# aparture_v2.net
KiCad netlist of a schematic drawn in EAGLE
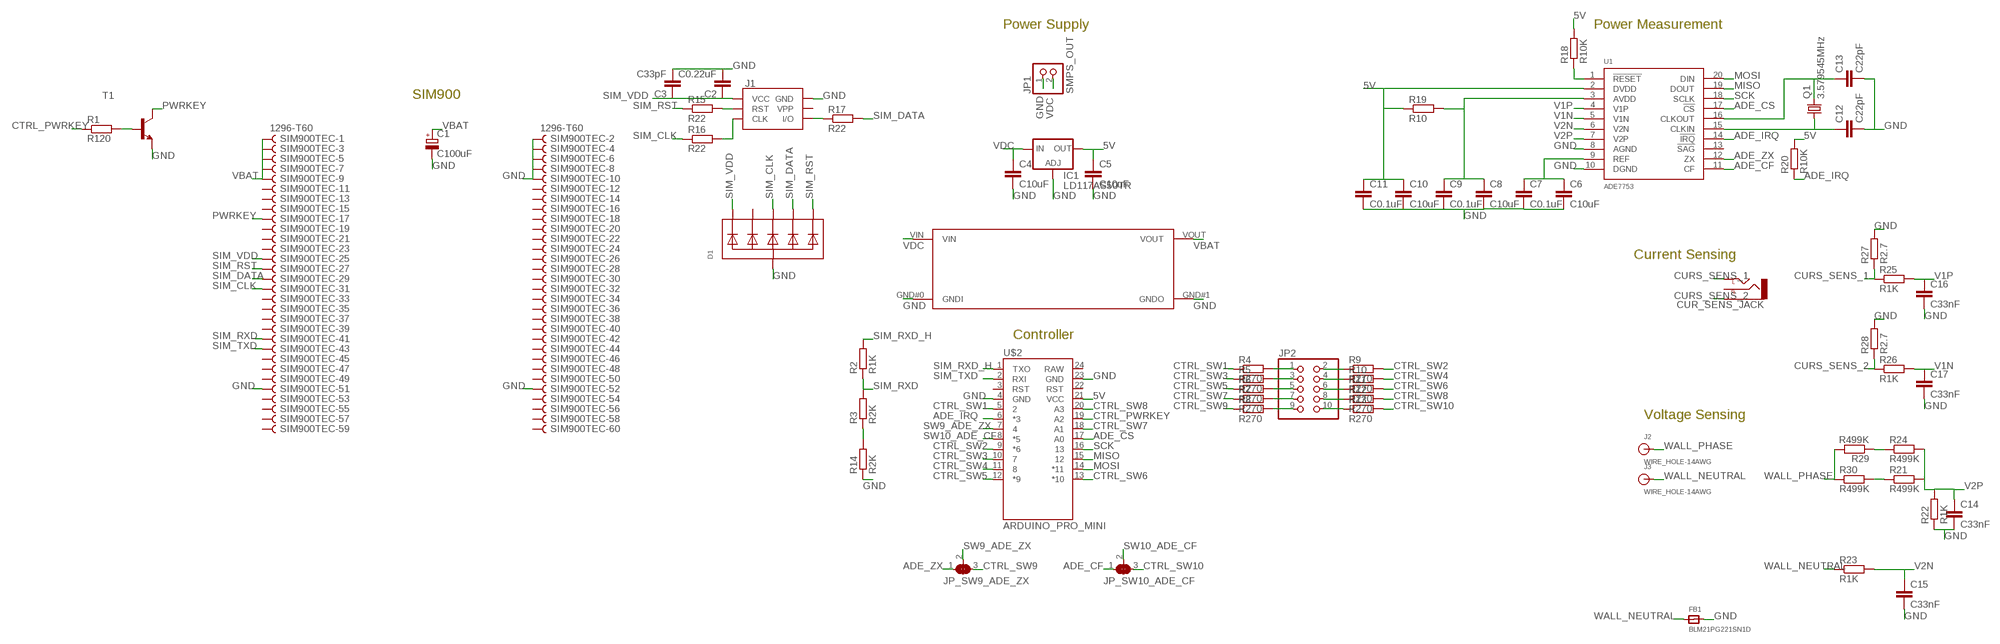
[diagram p0: schematic, sheet 1]

(export (version "E")
  (design (tool "Eeschema 10.0.6"))
  (components
    (comp (ref "C1")
      (value "C100uF")
      (footprint "eagle-import:153CLV-0605")
      (libsource (lib "eagle-import") (part "CPOL-EU153CLV-0605"))
    )
    (comp (ref "C2")
      (value "C0.22uF")
      (footprint "eagle-import:C0805")
      (libsource (lib "eagle-import") (part "C-EUC0805"))
    )
    (comp (ref "C3")
      (value "C33pF")
      (footprint "eagle-import:C0805")
      (libsource (lib "eagle-import") (part "C-EUC0805"))
    )
    (comp (ref "C4")
      (value "C10uF")
      (footprint "eagle-import:C0805")
      (libsource (lib "eagle-import") (part "C-EUC0805"))
    )
    (comp (ref "C5")
      (value "C10uF")
      (footprint "eagle-import:C0805")
      (libsource (lib "eagle-import") (part "C-EUC0805"))
    )
    (comp (ref "C6")
      (value "C10uF")
      (footprint "eagle-import:C0805")
      (libsource (lib "eagle-import") (part "C-EUC0805"))
    )
    (comp (ref "C7")
      (value "C0.1uF")
      (footprint "eagle-import:C0805")
      (libsource (lib "eagle-import") (part "C-EUC0805"))
    )
    (comp (ref "C8")
      (value "C10uF")
      (footprint "eagle-import:C0805")
      (libsource (lib "eagle-import") (part "C-EUC0805"))
    )
    (comp (ref "C9")
      (value "C0.1uF")
      (footprint "eagle-import:C0805")
      (libsource (lib "eagle-import") (part "C-EUC0805"))
    )
    (comp (ref "C10")
      (value "C10uF")
      (footprint "eagle-import:C0805")
      (libsource (lib "eagle-import") (part "C-EUC0805"))
    )
    (comp (ref "C11")
      (value "C0.1uF")
      (footprint "eagle-import:C0805")
      (libsource (lib "eagle-import") (part "C-EUC0805"))
    )
    (comp (ref "C12")
      (value "C22pF")
      (footprint "eagle-import:C0805")
      (libsource (lib "eagle-import") (part "C-EUC0805"))
    )
    (comp (ref "C13")
      (value "C22pF")
      (footprint "eagle-import:C0805")
      (libsource (lib "eagle-import") (part "C-EUC0805"))
    )
    (comp (ref "C14")
      (value "C33nF")
      (footprint "eagle-import:C0805")
      (libsource (lib "eagle-import") (part "C-EUC0805"))
    )
    (comp (ref "C15")
      (value "C33nF")
      (footprint "eagle-import:C0805")
      (libsource (lib "eagle-import") (part "C-EUC0805"))
    )
    (comp (ref "C16")
      (value "C33nF")
      (footprint "eagle-import:C0805")
      (libsource (lib "eagle-import") (part "C-EUC0805"))
    )
    (comp (ref "C17")
      (value "C33nF")
      (footprint "eagle-import:C0805")
      (libsource (lib "eagle-import") (part "C-EUC0805"))
    )
    (comp (ref "CUR_SENS_JACK")
      (value "AUDIO-JACKSMD2")
      (footprint "eagle-import:AUDIO-JACK-3.5MM-SMD")
      (libsource (lib "eagle-import") (part "AUDIO-JACKSMD2"))
    )
    (comp (ref "D1")
      (value "TVSARRAY_5LANE")
      (footprint "eagle-import:SOT363")
      (libsource (lib "eagle-import") (part "TVSARRAY_5LANE"))
    )
    (comp (ref "FB1")
      (value "BLM21PG221SN1D")
      (footprint "eagle-import:0805")
      (libsource (lib "eagle-import") (part "FERRITE0805"))
    )
    (comp (ref "IC1")
      (value "LD117AS50TR")
      (footprint "eagle-import:SOT223")
      (libsource (lib "eagle-import") (part "LD117A?S50TR"))
    )
    (comp (ref "J1")
      (value "SIMHOLDERSIM")
      (footprint "eagle-import:SIMHOLDER")
      (libsource (lib "eagle-import") (part "SIMHOLDERSIM"))
    )
    (comp (ref "J2")
      (value "WIRE_HOLE-14AWG")
      (footprint "eagle-import:WIRE_HOLE-14AWG")
      (libsource (lib "eagle-import") (part "WIRE_HOLE-14AWG"))
    )
    (comp (ref "J3")
      (value "WIRE_HOLE-14AWG")
      (footprint "eagle-import:WIRE_HOLE-14AWG")
      (libsource (lib "eagle-import") (part "WIRE_HOLE-14AWG"))
    )
    (comp (ref "JP1")
      (value "SMPS_OUT")
      (footprint "eagle-import:1X02")
      (libsource (lib "eagle-import") (part "PINHD-1X2"))
    )
    (comp (ref "JP2")
      (value "PINHD-2X5")
      (footprint "eagle-import:2X05")
      (libsource (lib "eagle-import") (part "PINHD-2X5"))
    )
    (comp (ref "JP_SW9_ADE_ZX")
      (value "SOLDERJUMPER_2WAY0603")
      (footprint "eagle-import:SOLDERJUMPER_2WAY_OPEN_0603")
      (libsource (lib "eagle-import") (part "SOLDERJUMPER_2WAY0603"))
    )
    (comp (ref "JP_SW10_ADE_CF")
      (value "SOLDERJUMPER_2WAY0603")
      (footprint "eagle-import:SOLDERJUMPER_2WAY_OPEN_0603")
      (libsource (lib "eagle-import") (part "SOLDERJUMPER_2WAY0603"))
    )
    (comp (ref "Q1")
      (value "3.579545MHz")
      (footprint "eagle-import:HC49_S")
      (libsource (lib "eagle-import") (part "CRYSTALHC49S"))
    )
    (comp (ref "R1")
      (value "R120")
      (footprint "eagle-import:R0805")
      (libsource (lib "eagle-import") (part "R-EU_R0805"))
    )
    (comp (ref "R2")
      (value "R1K")
      (footprint "eagle-import:M0805")
      (libsource (lib "eagle-import") (part "R-EU_M0805"))
    )
    (comp (ref "R3")
      (value "R2K")
      (footprint "eagle-import:M0805")
      (libsource (lib "eagle-import") (part "R-EU_M0805"))
    )
    (comp (ref "R4")
      (value "R270")
      (footprint "eagle-import:R0603")
      (libsource (lib "eagle-import") (part "R-EU_R0603"))
    )
    (comp (ref "R5")
      (value "R270")
      (footprint "eagle-import:R0603")
      (libsource (lib "eagle-import") (part "R-EU_R0603"))
    )
    (comp (ref "R6")
      (value "R270")
      (footprint "eagle-import:R0603")
      (libsource (lib "eagle-import") (part "R-EU_R0603"))
    )
    (comp (ref "R7")
      (value "R270")
      (footprint "eagle-import:R0603")
      (libsource (lib "eagle-import") (part "R-EU_R0603"))
    )
    (comp (ref "R8")
      (value "R270")
      (footprint "eagle-import:R0603")
      (libsource (lib "eagle-import") (part "R-EU_R0603"))
    )
    (comp (ref "R9")
      (value "R270")
      (footprint "eagle-import:R0603")
      (libsource (lib "eagle-import") (part "R-EU_R0603"))
    )
    (comp (ref "R10")
      (value "R270")
      (footprint "eagle-import:R0603")
      (libsource (lib "eagle-import") (part "R-EU_R0603"))
    )
    (comp (ref "R11")
      (value "R270")
      (footprint "eagle-import:R0603")
      (libsource (lib "eagle-import") (part "R-EU_R0603"))
    )
    (comp (ref "R12")
      (value "R270")
      (footprint "eagle-import:R0603")
      (libsource (lib "eagle-import") (part "R-EU_R0603"))
    )
    (comp (ref "R13")
      (value "R270")
      (footprint "eagle-import:R0603")
      (libsource (lib "eagle-import") (part "R-EU_R0603"))
    )
    (comp (ref "R14")
      (value "R2K")
      (footprint "eagle-import:M0805")
      (libsource (lib "eagle-import") (part "R-EU_M0805"))
    )
    (comp (ref "R15")
      (value "R22")
      (footprint "eagle-import:R0603")
      (libsource (lib "eagle-import") (part "R-EU_R0603"))
    )
    (comp (ref "R16")
      (value "R22")
      (footprint "eagle-import:R0603")
      (libsource (lib "eagle-import") (part "R-EU_R0603"))
    )
    (comp (ref "R17")
      (value "R22")
      (footprint "eagle-import:R0603")
      (libsource (lib "eagle-import") (part "R-EU_R0603"))
    )
    (comp (ref "R18")
      (value "R10K")
      (footprint "eagle-import:R0805")
      (libsource (lib "eagle-import") (part "R-EU_R0805"))
    )
    (comp (ref "R19")
      (value "R10")
      (footprint "eagle-import:R0805")
      (libsource (lib "eagle-import") (part "R-EU_R0805"))
    )
    (comp (ref "R20")
      (value "R10K")
      (footprint "eagle-import:R0805")
      (libsource (lib "eagle-import") (part "R-EU_R0805"))
    )
    (comp (ref "R21")
      (value "R499K")
      (footprint "eagle-import:R0805")
      (libsource (lib "eagle-import") (part "R-EU_R0805"))
    )
    (comp (ref "R22")
      (value "R1K")
      (footprint "eagle-import:R0805")
      (libsource (lib "eagle-import") (part "R-EU_R0805"))
    )
    (comp (ref "R23")
      (value "R1K")
      (footprint "eagle-import:R0805")
      (libsource (lib "eagle-import") (part "R-EU_R0805"))
    )
    (comp (ref "R24")
      (value "R499K")
      (footprint "eagle-import:0309V")
      (libsource (lib "eagle-import") (part "R-EU_0309/V"))
    )
    (comp (ref "R25")
      (value "R1K")
      (footprint "eagle-import:R0805")
      (libsource (lib "eagle-import") (part "R-EU_R0805"))
    )
    (comp (ref "R26")
      (value "R1K")
      (footprint "eagle-import:R0805")
      (libsource (lib "eagle-import") (part "R-EU_R0805"))
    )
    (comp (ref "R27")
      (value "R2.7")
      (footprint "eagle-import:0309V")
      (libsource (lib "eagle-import") (part "R-EU_0309/V"))
    )
    (comp (ref "R28")
      (value "R2.7")
      (footprint "eagle-import:0309V")
      (libsource (lib "eagle-import") (part "R-EU_0309/V"))
    )
    (comp (ref "R29")
      (value "R499K")
      (footprint "eagle-import:0309V")
      (libsource (lib "eagle-import") (part "R-EU_0309/V"))
    )
    (comp (ref "R30")
      (value "R499K")
      (footprint "eagle-import:R0805")
      (libsource (lib "eagle-import") (part "R-EU_R0805"))
    )
    (comp (ref "SIM900TEC")
      (value "1296-T60")
      (footprint "eagle-import:1296-60")
      (libsource (lib "eagle-import") (part "1296-T60"))
    )
    (comp (ref "T1")
      (value "MMBT2222ALT1-NPN-SOT23-BEC")
      (footprint "eagle-import:SOT23-BEC")
      (libsource (lib "eagle-import") (part "-NPN-SOT23-BECMMBT2222ALT1"))
    )
    (comp (ref "U$1")
      (value "DCDCMODULE")
      (footprint "eagle-import:DCDCMODULE")
      (libsource (lib "eagle-import") (part "DCDCMODULE"))
    )
    (comp (ref "U$2")
      (value "ARDUINO_PRO_MINI")
      (footprint "eagle-import:ARDUINO_PRO_MINI")
      (libsource (lib "eagle-import") (part "ARDUINO_PRO_MINI"))
    )
    (comp (ref "U1")
      (value "ADE7753")
      (footprint "eagle-import:SSOP-20")
      (libsource (lib "eagle-import") (part "ADE7753"))
    )
  )
  (nets
    (net (code "1") (name "/5V") (class "Default")
      (node (ref "C10") (pin "1") (pinfunction "1_1") (pintype "passive"))
      (node (ref "C11") (pin "1") (pinfunction "1_1") (pintype "passive"))
      (node (ref "C5") (pin "1") (pinfunction "1_1") (pintype "passive"))
      (node (ref "IC1") (pin "4") (pinfunction "OUT_4") (pintype "passive"))
      (node (ref "R18") (pin "2") (pinfunction "2_2") (pintype "passive"))
      (node (ref "R19") (pin "1") (pinfunction "1_1") (pintype "passive"))
      (node (ref "R20") (pin "2") (pinfunction "2_2") (pintype "passive"))
      (node (ref "U$2") (pin "21") (pinfunction "VCC_21") (pintype "bidirectional"))
      (node (ref "U1") (pin "2") (pinfunction "DVDD_2") (pintype "bidirectional"))
    )
    (net (code "2") (name "/ADE_CF") (class "Default")
      (node (ref "JP_SW10_ADE_CF") (pin "1") (pinfunction "1_1") (pintype "passive"))
      (node (ref "U1") (pin "11") (pinfunction "CF_11") (pintype "bidirectional"))
    )
    (net (code "3") (name "/ADE_CS") (class "Default")
      (node (ref "U$2") (pin "17") (pinfunction "A0_17") (pintype "bidirectional"))
      (node (ref "U1") (pin "17") (pinfunction "~{CS}_17") (pintype "bidirectional"))
    )
    (net (code "4") (name "/ADE_IRQ") (class "Default")
      (node (ref "R20") (pin "1") (pinfunction "1_1") (pintype "passive"))
      (node (ref "U$2") (pin "6") (pinfunction "*3_6") (pintype "bidirectional"))
      (node (ref "U1") (pin "14") (pinfunction "~{IRQ}_14") (pintype "bidirectional"))
    )
    (net (code "5") (name "/ADE_ZX") (class "Default")
      (node (ref "JP_SW9_ADE_ZX") (pin "1") (pinfunction "1_1") (pintype "passive"))
      (node (ref "U1") (pin "12") (pinfunction "ZX_12") (pintype "bidirectional"))
    )
    (net (code "6") (name "/CTRL_PWRKEY") (class "Default")
      (node (ref "R1") (pin "1") (pinfunction "1_1") (pintype "passive"))
      (node (ref "U$2") (pin "19") (pinfunction "A2_19") (pintype "bidirectional"))
    )
    (net (code "7") (name "/CTRL_SW1") (class "Default")
      (node (ref "R4") (pin "1") (pinfunction "1_1") (pintype "passive"))
      (node (ref "U$2") (pin "5") (pinfunction "2_5") (pintype "bidirectional"))
    )
    (net (code "8") (name "/CTRL_SW2") (class "Default")
      (node (ref "R9") (pin "2") (pinfunction "2_2") (pintype "passive"))
      (node (ref "U$2") (pin "9") (pinfunction "*6_9") (pintype "bidirectional"))
    )
    (net (code "9") (name "/CTRL_SW3") (class "Default")
      (node (ref "R5") (pin "1") (pinfunction "1_1") (pintype "passive"))
      (node (ref "U$2") (pin "10") (pinfunction "7_10") (pintype "bidirectional"))
    )
    (net (code "10") (name "/CTRL_SW4") (class "Default")
      (node (ref "R10") (pin "2") (pinfunction "2_2") (pintype "passive"))
      (node (ref "U$2") (pin "11") (pinfunction "8_11") (pintype "bidirectional"))
    )
    (net (code "11") (name "/CTRL_SW5") (class "Default")
      (node (ref "R6") (pin "1") (pinfunction "1_1") (pintype "passive"))
      (node (ref "U$2") (pin "12") (pinfunction "*9_12") (pintype "bidirectional"))
    )
    (net (code "12") (name "/CTRL_SW6") (class "Default")
      (node (ref "R11") (pin "2") (pinfunction "2_2") (pintype "passive"))
      (node (ref "U$2") (pin "13") (pinfunction "*10_13") (pintype "bidirectional"))
    )
    (net (code "13") (name "/CTRL_SW7") (class "Default")
      (node (ref "R7") (pin "1") (pinfunction "1_1") (pintype "passive"))
      (node (ref "U$2") (pin "18") (pinfunction "A1_18") (pintype "bidirectional"))
    )
    (net (code "14") (name "/CTRL_SW8") (class "Default")
      (node (ref "R12") (pin "2") (pinfunction "2_2") (pintype "passive"))
      (node (ref "U$2") (pin "20") (pinfunction "A3_20") (pintype "bidirectional"))
    )
    (net (code "15") (name "/CTRL_SW9") (class "Default")
      (node (ref "JP_SW9_ADE_ZX") (pin "3") (pinfunction "3_3") (pintype "passive"))
      (node (ref "R8") (pin "1") (pinfunction "1_1") (pintype "passive"))
    )
    (net (code "16") (name "/CTRL_SW10") (class "Default")
      (node (ref "JP_SW10_ADE_CF") (pin "3") (pinfunction "3_3") (pintype "passive"))
      (node (ref "R13") (pin "2") (pinfunction "2_2") (pintype "passive"))
    )
    (net (code "17") (name "/CURS_SENS_1") (class "Default")
      (node (ref "CUR_SENS_JACK") (pin "TIP") (pinfunction "LEFT_TIP") (pintype "bidirectional"))
      (node (ref "R25") (pin "1") (pinfunction "1_1") (pintype "passive"))
      (node (ref "R27") (pin "1") (pinfunction "1_1") (pintype "passive"))
    )
    (net (code "18") (name "/CURS_SENS_2") (class "Default")
      (node (ref "CUR_SENS_JACK") (pin "SLEEVE") (pinfunction "SLEEVE_SLEEVE") (pintype "bidirectional"))
      (node (ref "R26") (pin "1") (pinfunction "1_1") (pintype "passive"))
      (node (ref "R28") (pin "1") (pinfunction "1_1") (pintype "passive"))
    )
    (net (code "19") (name "/GND") (class "Default")
      (node (ref "C1") (pin "-") (pinfunction "-_-") (pintype "passive"))
      (node (ref "C10") (pin "2") (pinfunction "2_2") (pintype "passive"))
      (node (ref "C11") (pin "2") (pinfunction "2_2") (pintype "passive"))
      (node (ref "C12") (pin "2") (pinfunction "2_2") (pintype "passive"))
      (node (ref "C13") (pin "2") (pinfunction "2_2") (pintype "passive"))
      (node (ref "C14") (pin "2") (pinfunction "2_2") (pintype "passive"))
      (node (ref "C15") (pin "2") (pinfunction "2_2") (pintype "passive"))
      (node (ref "C16") (pin "2") (pinfunction "2_2") (pintype "passive"))
      (node (ref "C17") (pin "2") (pinfunction "2_2") (pintype "passive"))
      (node (ref "C2") (pin "2") (pinfunction "2_2") (pintype "passive"))
      (node (ref "C3") (pin "2") (pinfunction "2_2") (pintype "passive"))
      (node (ref "C4") (pin "2") (pinfunction "2_2") (pintype "passive"))
      (node (ref "C5") (pin "2") (pinfunction "2_2") (pintype "passive"))
      (node (ref "C6") (pin "2") (pinfunction "2_2") (pintype "passive"))
      (node (ref "C7") (pin "2") (pinfunction "2_2") (pintype "passive"))
      (node (ref "C8") (pin "2") (pinfunction "2_2") (pintype "passive"))
      (node (ref "C9") (pin "2") (pinfunction "2_2") (pintype "passive"))
      (node (ref "D1") (pin "2") (pinfunction "A_2") (pintype "passive"))
      (node (ref "FB1") (pin "2") (pinfunction "P$2_2") (pintype "passive"))
      (node (ref "IC1") (pin "1") (pinfunction "ADJ_1") (pintype "input"))
      (node (ref "J1") (pin "C5") (pinfunction "GND_C5") (pintype "power_in"))
      (node (ref "JP1") (pin "1") (pinfunction "1_1") (pintype "passive"))
      (node (ref "R14") (pin "1") (pinfunction "1_1") (pintype "passive"))
      (node (ref "R22") (pin "1") (pinfunction "1_1") (pintype "passive"))
      (node (ref "R27") (pin "2") (pinfunction "2_2") (pintype "passive"))
      (node (ref "R28") (pin "2") (pinfunction "2_2") (pintype "passive"))
      (node (ref "SIM900TEC") (pin "10") (pinfunction "B_10") (pintype "passive"))
      (node (ref "SIM900TEC") (pin "2") (pinfunction "B_2") (pintype "passive"))
      (node (ref "SIM900TEC") (pin "4") (pinfunction "B_4") (pintype "passive"))
      (node (ref "SIM900TEC") (pin "51") (pinfunction "B_51") (pintype "passive"))
      (node (ref "SIM900TEC") (pin "52") (pinfunction "B_52") (pintype "passive"))
      (node (ref "SIM900TEC") (pin "6") (pinfunction "B_6") (pintype "passive"))
      (node (ref "SIM900TEC") (pin "8") (pinfunction "B_8") (pintype "passive"))
      (node (ref "T1") (pin "E") (pinfunction "E_E") (pintype "passive"))
      (node (ref "U$1") (pin "GND#0") (pinfunction "GNDI_GND#0") (pintype "bidirectional"))
      (node (ref "U$1") (pin "GND#1") (pinfunction "GNDO_GND#1") (pintype "bidirectional"))
      (node (ref "U$2") (pin "23") (pinfunction "GND_23") (pintype "bidirectional"))
      (node (ref "U$2") (pin "4") (pinfunction "GND_4") (pintype "bidirectional"))
      (node (ref "U1") (pin "10") (pinfunction "DGND_10") (pintype "bidirectional"))
      (node (ref "U1") (pin "8") (pinfunction "AGND_8") (pintype "bidirectional"))
    )
    (net (code "20") (name "/MISO") (class "Default")
      (node (ref "U$2") (pin "15") (pinfunction "12_15") (pintype "bidirectional"))
      (node (ref "U1") (pin "19") (pinfunction "DOUT_19") (pintype "bidirectional"))
    )
    (net (code "21") (name "/MOSI") (class "Default")
      (node (ref "U$2") (pin "14") (pinfunction "*11_14") (pintype "bidirectional"))
      (node (ref "U1") (pin "20") (pinfunction "DIN_20") (pintype "bidirectional"))
    )
    (net (code "22") (name "/PWRKEY") (class "Default")
      (node (ref "SIM900TEC") (pin "17") (pinfunction "B_17") (pintype "passive"))
      (node (ref "T1") (pin "C") (pinfunction "C_C") (pintype "passive"))
    )
    (net (code "23") (name "/SCK") (class "Default")
      (node (ref "U$2") (pin "16") (pinfunction "13_16") (pintype "bidirectional"))
      (node (ref "U1") (pin "18") (pinfunction "SCLK_18") (pintype "bidirectional"))
    )
    (net (code "24") (name "/SIM_CLK") (class "Default")
      (node (ref "D1") (pin "4") (pinfunction "C3_4") (pintype "passive"))
      (node (ref "R16") (pin "1") (pinfunction "1_1") (pintype "passive"))
      (node (ref "SIM900TEC") (pin "31") (pinfunction "B_31") (pintype "passive"))
    )
    (net (code "25") (name "/SIM_DATA") (class "Default")
      (node (ref "D1") (pin "5") (pinfunction "C4_5") (pintype "passive"))
      (node (ref "R17") (pin "2") (pinfunction "2_2") (pintype "passive"))
      (node (ref "SIM900TEC") (pin "29") (pinfunction "B_29") (pintype "passive"))
    )
    (net (code "26") (name "/SIM_RST") (class "Default")
      (node (ref "D1") (pin "6") (pinfunction "C5_6") (pintype "passive"))
      (node (ref "R15") (pin "1") (pinfunction "1_1") (pintype "passive"))
      (node (ref "SIM900TEC") (pin "27") (pinfunction "B_27") (pintype "passive"))
    )
    (net (code "27") (name "/SIM_RXD") (class "Default")
      (node (ref "R2") (pin "1") (pinfunction "1_1") (pintype "passive"))
      (node (ref "R3") (pin "2") (pinfunction "2_2") (pintype "passive"))
      (node (ref "SIM900TEC") (pin "41") (pinfunction "B_41") (pintype "passive"))
    )
    (net (code "28") (name "/SIM_RXD_H") (class "Default")
      (node (ref "R2") (pin "2") (pinfunction "2_2") (pintype "passive"))
      (node (ref "U$2") (pin "1") (pinfunction "TXO_1") (pintype "bidirectional"))
    )
    (net (code "29") (name "/SIM_TXD") (class "Default")
      (node (ref "SIM900TEC") (pin "43") (pinfunction "B_43") (pintype "passive"))
      (node (ref "U$2") (pin "2") (pinfunction "RXI_2") (pintype "bidirectional"))
    )
    (net (code "30") (name "/SIM_VDD") (class "Default")
      (node (ref "C2") (pin "1") (pinfunction "1_1") (pintype "passive"))
      (node (ref "C3") (pin "1") (pinfunction "1_1") (pintype "passive"))
      (node (ref "D1") (pin "1") (pinfunction "C1_1") (pintype "passive"))
      (node (ref "J1") (pin "C1") (pinfunction "VCC_C1") (pintype "power_in"))
      (node (ref "SIM900TEC") (pin "25") (pinfunction "B_25") (pintype "passive"))
    )
    (net (code "31") (name "/SW9_ADE_ZX") (class "Default")
      (node (ref "JP_SW9_ADE_ZX") (pin "2") (pinfunction "2_2") (pintype "passive"))
      (node (ref "U$2") (pin "7") (pinfunction "4_7") (pintype "bidirectional"))
    )
    (net (code "32") (name "/SW10_ADE_CF") (class "Default")
      (node (ref "JP_SW10_ADE_CF") (pin "2") (pinfunction "2_2") (pintype "passive"))
      (node (ref "U$2") (pin "8") (pinfunction "*5_8") (pintype "bidirectional"))
    )
    (net (code "33") (name "/V1N") (class "Default")
      (node (ref "C17") (pin "1") (pinfunction "1_1") (pintype "passive"))
      (node (ref "R26") (pin "2") (pinfunction "2_2") (pintype "passive"))
      (node (ref "U1") (pin "5") (pinfunction "V1N_5") (pintype "bidirectional"))
    )
    (net (code "34") (name "/V1P") (class "Default")
      (node (ref "C16") (pin "1") (pinfunction "1_1") (pintype "passive"))
      (node (ref "R25") (pin "2") (pinfunction "2_2") (pintype "passive"))
      (node (ref "U1") (pin "4") (pinfunction "V1P_4") (pintype "bidirectional"))
    )
    (net (code "35") (name "/V2N") (class "Default")
      (node (ref "C15") (pin "1") (pinfunction "1_1") (pintype "passive"))
      (node (ref "R23") (pin "2") (pinfunction "2_2") (pintype "passive"))
      (node (ref "U1") (pin "6") (pinfunction "V2N_6") (pintype "bidirectional"))
    )
    (net (code "36") (name "/V2P") (class "Default")
      (node (ref "C14") (pin "1") (pinfunction "1_1") (pintype "passive"))
      (node (ref "R21") (pin "2") (pinfunction "2_2") (pintype "passive"))
      (node (ref "R22") (pin "2") (pinfunction "2_2") (pintype "passive"))
      (node (ref "R24") (pin "2") (pinfunction "2_2") (pintype "passive"))
      (node (ref "U1") (pin "7") (pinfunction "V2P_7") (pintype "bidirectional"))
    )
    (net (code "37") (name "/VBAT") (class "Default")
      (node (ref "C1") (pin "+") (pinfunction "+_+") (pintype "passive"))
      (node (ref "SIM900TEC") (pin "1") (pinfunction "B_1") (pintype "passive"))
      (node (ref "SIM900TEC") (pin "3") (pinfunction "B_3") (pintype "passive"))
      (node (ref "SIM900TEC") (pin "5") (pinfunction "B_5") (pintype "passive"))
      (node (ref "SIM900TEC") (pin "7") (pinfunction "B_7") (pintype "passive"))
      (node (ref "SIM900TEC") (pin "9") (pinfunction "B_9") (pintype "passive"))
      (node (ref "U$1") (pin "VOUT") (pinfunction "VOUT_VOUT") (pintype "bidirectional"))
    )
    (net (code "38") (name "/VDC") (class "Default")
      (node (ref "C4") (pin "1") (pinfunction "1_1") (pintype "passive"))
      (node (ref "IC1") (pin "3") (pinfunction "IN_3") (pintype "input"))
      (node (ref "JP1") (pin "2") (pinfunction "2_2") (pintype "passive"))
      (node (ref "U$1") (pin "VIN") (pinfunction "VIN_VIN") (pintype "bidirectional"))
    )
    (net (code "39") (name "/WALL_NEUTRAL") (class "Default")
      (node (ref "FB1") (pin "1") (pinfunction "P$1_1") (pintype "passive"))
      (node (ref "J3") (pin "P$1") (pinfunction "P$1_P$1") (pintype "bidirectional"))
      (node (ref "R23") (pin "1") (pinfunction "1_1") (pintype "passive"))
    )
    (net (code "40") (name "/WALL_PHASE") (class "Default")
      (node (ref "J2") (pin "P$1") (pinfunction "P$1_P$1") (pintype "bidirectional"))
      (node (ref "R29") (pin "2") (pinfunction "2_2") (pintype "passive"))
      (node (ref "R30") (pin "1") (pinfunction "1_1") (pintype "passive"))
    )
    (net (code "41") (name "Net-(J1-CLK)") (class "Default")
      (node (ref "J1") (pin "C3") (pinfunction "CLK_C3") (pintype "input"))
      (node (ref "R16") (pin "2") (pinfunction "2_2") (pintype "passive"))
    )
    (net (code "42") (name "Net-(J1-I{slash}O)") (class "Default")
      (node (ref "J1") (pin "C7") (pinfunction "I/O_C7") (pintype "bidirectional"))
      (node (ref "R17") (pin "1") (pinfunction "1_1") (pintype "passive"))
    )
    (net (code "43") (name "Net-(J1-RST)") (class "Default")
      (node (ref "J1") (pin "C2") (pinfunction "RST_C2") (pintype "input"))
      (node (ref "R15") (pin "2") (pinfunction "2_2") (pintype "passive"))
    )
    (net (code "44") (name "Net-(JP2-Pad1)") (class "Default")
      (node (ref "JP2") (pin "1") (pinfunction "1_1") (pintype "passive"))
      (node (ref "R4") (pin "2") (pinfunction "2_2") (pintype "passive"))
    )
    (net (code "45") (name "Net-(JP2-Pad2)") (class "Default")
      (node (ref "JP2") (pin "2") (pinfunction "2_2") (pintype "passive"))
      (node (ref "R9") (pin "1") (pinfunction "1_1") (pintype "passive"))
    )
    (net (code "46") (name "Net-(JP2-Pad3)") (class "Default")
      (node (ref "JP2") (pin "3") (pinfunction "3_3") (pintype "passive"))
      (node (ref "R5") (pin "2") (pinfunction "2_2") (pintype "passive"))
    )
    (net (code "47") (name "Net-(JP2-Pad4)") (class "Default")
      (node (ref "JP2") (pin "4") (pinfunction "4_4") (pintype "passive"))
      (node (ref "R10") (pin "1") (pinfunction "1_1") (pintype "passive"))
    )
    (net (code "48") (name "Net-(JP2-Pad5)") (class "Default")
      (node (ref "JP2") (pin "5") (pinfunction "5_5") (pintype "passive"))
      (node (ref "R6") (pin "2") (pinfunction "2_2") (pintype "passive"))
    )
    (net (code "49") (name "Net-(JP2-Pad6)") (class "Default")
      (node (ref "JP2") (pin "6") (pinfunction "6_6") (pintype "passive"))
      (node (ref "R11") (pin "1") (pinfunction "1_1") (pintype "passive"))
    )
    (net (code "50") (name "Net-(JP2-Pad7)") (class "Default")
      (node (ref "JP2") (pin "7") (pinfunction "7_7") (pintype "passive"))
      (node (ref "R7") (pin "2") (pinfunction "2_2") (pintype "passive"))
    )
    (net (code "51") (name "Net-(JP2-Pad8)") (class "Default")
      (node (ref "JP2") (pin "8") (pinfunction "8_8") (pintype "passive"))
      (node (ref "R12") (pin "1") (pinfunction "1_1") (pintype "passive"))
    )
    (net (code "52") (name "Net-(JP2-Pad9)") (class "Default")
      (node (ref "JP2") (pin "9") (pinfunction "9_9") (pintype "passive"))
      (node (ref "R8") (pin "2") (pinfunction "2_2") (pintype "passive"))
    )
    (net (code "53") (name "Net-(JP2-Pad10)") (class "Default")
      (node (ref "JP2") (pin "10") (pinfunction "10_10") (pintype "passive"))
      (node (ref "R13") (pin "1") (pinfunction "1_1") (pintype "passive"))
    )
    (net (code "54") (name "Net-(R1-Pad2)") (class "Default")
      (node (ref "R1") (pin "2") (pinfunction "2_2") (pintype "passive"))
      (node (ref "T1") (pin "B") (pinfunction "B_B") (pintype "passive"))
    )
    (net (code "55") (name "Net-(R14-Pad2)") (class "Default")
      (node (ref "R14") (pin "2") (pinfunction "2_2") (pintype "passive"))
      (node (ref "R3") (pin "1") (pinfunction "1_1") (pintype "passive"))
    )
    (net (code "56") (name "Net-(R21-Pad1)") (class "Default")
      (node (ref "R21") (pin "1") (pinfunction "1_1") (pintype "passive"))
      (node (ref "R30") (pin "2") (pinfunction "2_2") (pintype "passive"))
    )
    (net (code "57") (name "Net-(R24-Pad1)") (class "Default")
      (node (ref "R24") (pin "1") (pinfunction "1_1") (pintype "passive"))
      (node (ref "R29") (pin "1") (pinfunction "1_1") (pintype "passive"))
    )
    (net (code "58") (name "Net-(U1-AVDD)") (class "Default")
      (node (ref "C8") (pin "1") (pinfunction "1_1") (pintype "passive"))
      (node (ref "C9") (pin "1") (pinfunction "1_1") (pintype "passive"))
      (node (ref "R19") (pin "2") (pinfunction "2_2") (pintype "passive"))
      (node (ref "U1") (pin "3") (pinfunction "AVDD_3") (pintype "bidirectional"))
    )
    (net (code "59") (name "Net-(U1-CLKIN)") (class "Default")
      (node (ref "C12") (pin "1") (pinfunction "1_1") (pintype "passive"))
      (node (ref "Q1") (pin "1") (pinfunction "1_1") (pintype "passive"))
      (node (ref "U1") (pin "15") (pinfunction "CLKIN_15") (pintype "bidirectional"))
    )
    (net (code "60") (name "Net-(U1-CLKOUT)") (class "Default")
      (node (ref "C13") (pin "1") (pinfunction "1_1") (pintype "passive"))
      (node (ref "Q1") (pin "2") (pinfunction "2_2") (pintype "passive"))
      (node (ref "U1") (pin "16") (pinfunction "CLKOUT_16") (pintype "bidirectional"))
    )
    (net (code "61") (name "Net-(U1-REF)") (class "Default")
      (node (ref "C6") (pin "1") (pinfunction "1_1") (pintype "passive"))
      (node (ref "C7") (pin "1") (pinfunction "1_1") (pintype "passive"))
      (node (ref "U1") (pin "9") (pinfunction "REF_9") (pintype "bidirectional"))
    )
    (net (code "62") (name "Net-(U1-~{RESET})") (class "Default")
      (node (ref "R18") (pin "1") (pinfunction "1_1") (pintype "passive"))
      (node (ref "U1") (pin "1") (pinfunction "~{RESET}_1") (pintype "bidirectional"))
    )
    (net (code "63") (name "unconnected-(CUR_SENS_JACK-RIGHT-PadRING)") (class "Default")
      (node (ref "CUR_SENS_JACK") (pin "RING") (pinfunction "RIGHT_RING") (pintype "bidirectional"))
    )
    (net (code "64") (name "unconnected-(D1-C2-Pad3)") (class "Default")
      (node (ref "D1") (pin "3") (pinfunction "C2_3") (pintype "passive"))
    )
    (net (code "65") (name "unconnected-(J1-VPP-PadC6)") (class "Default")
      (node (ref "J1") (pin "C6") (pinfunction "VPP_C6") (pintype "input"))
    )
    (net (code "66") (name "unconnected-(SIM900TECAA-B-Pad33)") (class "Default")
      (node (ref "SIM900TEC") (pin "33") (pinfunction "B_33") (pintype "passive"))
    )
    (net (code "67") (name "unconnected-(SIM900TECAB-B-Pad34)") (class "Default")
      (node (ref "SIM900TEC") (pin "34") (pinfunction "B_34") (pintype "passive"))
    )
    (net (code "68") (name "unconnected-(SIM900TECAC-B-Pad35)") (class "Default")
      (node (ref "SIM900TEC") (pin "35") (pinfunction "B_35") (pintype "passive"))
    )
    (net (code "69") (name "unconnected-(SIM900TECAD-B-Pad36)") (class "Default")
      (node (ref "SIM900TEC") (pin "36") (pinfunction "B_36") (pintype "passive"))
    )
    (net (code "70") (name "unconnected-(SIM900TECAE-B-Pad37)") (class "Default")
      (node (ref "SIM900TEC") (pin "37") (pinfunction "B_37") (pintype "passive"))
    )
    (net (code "71") (name "unconnected-(SIM900TECAF-B-Pad38)") (class "Default")
      (node (ref "SIM900TEC") (pin "38") (pinfunction "B_38") (pintype "passive"))
    )
    (net (code "72") (name "unconnected-(SIM900TECAG-B-Pad39)") (class "Default")
      (node (ref "SIM900TEC") (pin "39") (pinfunction "B_39") (pintype "passive"))
    )
    (net (code "73") (name "unconnected-(SIM900TECAI-B-Pad40)") (class "Default")
      (node (ref "SIM900TEC") (pin "40") (pinfunction "B_40") (pintype "passive"))
    )
    (net (code "74") (name "unconnected-(SIM900TECAK-B-Pad42)") (class "Default")
      (node (ref "SIM900TEC") (pin "42") (pinfunction "B_42") (pintype "passive"))
    )
    (net (code "75") (name "unconnected-(SIM900TECAM-B-Pad44)") (class "Default")
      (node (ref "SIM900TEC") (pin "44") (pinfunction "B_44") (pintype "passive"))
    )
    (net (code "76") (name "unconnected-(SIM900TECAN-B-Pad45)") (class "Default")
      (node (ref "SIM900TEC") (pin "45") (pinfunction "B_45") (pintype "passive"))
    )
    (net (code "77") (name "unconnected-(SIM900TECAO-B-Pad46)") (class "Default")
      (node (ref "SIM900TEC") (pin "46") (pinfunction "B_46") (pintype "passive"))
    )
    (net (code "78") (name "unconnected-(SIM900TECAP-B-Pad47)") (class "Default")
      (node (ref "SIM900TEC") (pin "47") (pinfunction "B_47") (pintype "passive"))
    )
    (net (code "79") (name "unconnected-(SIM900TECAQ-B-Pad48)") (class "Default")
      (node (ref "SIM900TEC") (pin "48") (pinfunction "B_48") (pintype "passive"))
    )
    (net (code "80") (name "unconnected-(SIM900TECAR-B-Pad49)") (class "Default")
      (node (ref "SIM900TEC") (pin "49") (pinfunction "B_49") (pintype "passive"))
    )
    (net (code "81") (name "unconnected-(SIM900TECAT-B-Pad50)") (class "Default")
      (node (ref "SIM900TEC") (pin "50") (pinfunction "B_50") (pintype "passive"))
    )
    (net (code "82") (name "unconnected-(SIM900TECAW-B-Pad53)") (class "Default")
      (node (ref "SIM900TEC") (pin "53") (pinfunction "B_53") (pintype "passive"))
    )
    (net (code "83") (name "unconnected-(SIM900TECAX-B-Pad54)") (class "Default")
      (node (ref "SIM900TEC") (pin "54") (pinfunction "B_54") (pintype "passive"))
    )
    (net (code "84") (name "unconnected-(SIM900TECAY-B-Pad55)") (class "Default")
      (node (ref "SIM900TEC") (pin "55") (pinfunction "B_55") (pintype "passive"))
    )
    (net (code "85") (name "unconnected-(SIM900TECAZ-B-Pad56)") (class "Default")
      (node (ref "SIM900TEC") (pin "56") (pinfunction "B_56") (pintype "passive"))
    )
    (net (code "86") (name "unconnected-(SIM900TECBA-B-Pad57)") (class "Default")
      (node (ref "SIM900TEC") (pin "57") (pinfunction "B_57") (pintype "passive"))
    )
    (net (code "87") (name "unconnected-(SIM900TECBB-B-Pad58)") (class "Default")
      (node (ref "SIM900TEC") (pin "58") (pinfunction "B_58") (pintype "passive"))
    )
    (net (code "88") (name "unconnected-(SIM900TECBC-B-Pad59)") (class "Default")
      (node (ref "SIM900TEC") (pin "59") (pinfunction "B_59") (pintype "passive"))
    )
    (net (code "89") (name "unconnected-(SIM900TECBE-B-Pad60)") (class "Default")
      (node (ref "SIM900TEC") (pin "60") (pinfunction "B_60") (pintype "passive"))
    )
    (net (code "90") (name "unconnected-(SIM900TECC-B-Pad11)") (class "Default")
      (node (ref "SIM900TEC") (pin "11") (pinfunction "B_11") (pintype "passive"))
    )
    (net (code "91") (name "unconnected-(SIM900TECD-B-Pad12)") (class "Default")
      (node (ref "SIM900TEC") (pin "12") (pinfunction "B_12") (pintype "passive"))
    )
    (net (code "92") (name "unconnected-(SIM900TECE-B-Pad13)") (class "Default")
      (node (ref "SIM900TEC") (pin "13") (pinfunction "B_13") (pintype "passive"))
    )
    (net (code "93") (name "unconnected-(SIM900TECF-B-Pad14)") (class "Default")
      (node (ref "SIM900TEC") (pin "14") (pinfunction "B_14") (pintype "passive"))
    )
    (net (code "94") (name "unconnected-(SIM900TECG-B-Pad15)") (class "Default")
      (node (ref "SIM900TEC") (pin "15") (pinfunction "B_15") (pintype "passive"))
    )
    (net (code "95") (name "unconnected-(SIM900TECH-B-Pad16)") (class "Default")
      (node (ref "SIM900TEC") (pin "16") (pinfunction "B_16") (pintype "passive"))
    )
    (net (code "96") (name "unconnected-(SIM900TECJ-B-Pad18)") (class "Default")
      (node (ref "SIM900TEC") (pin "18") (pinfunction "B_18") (pintype "passive"))
    )
    (net (code "97") (name "unconnected-(SIM900TECK-B-Pad19)") (class "Default")
      (node (ref "SIM900TEC") (pin "19") (pinfunction "B_19") (pintype "passive"))
    )
    (net (code "98") (name "unconnected-(SIM900TECM-B-Pad20)") (class "Default")
      (node (ref "SIM900TEC") (pin "20") (pinfunction "B_20") (pintype "passive"))
    )
    (net (code "99") (name "unconnected-(SIM900TECN-B-Pad21)") (class "Default")
      (node (ref "SIM900TEC") (pin "21") (pinfunction "B_21") (pintype "passive"))
    )
    (net (code "100") (name "unconnected-(SIM900TECO-B-Pad22)") (class "Default")
      (node (ref "SIM900TEC") (pin "22") (pinfunction "B_22") (pintype "passive"))
    )
    (net (code "101") (name "unconnected-(SIM900TECP-B-Pad23)") (class "Default")
      (node (ref "SIM900TEC") (pin "23") (pinfunction "B_23") (pintype "passive"))
    )
    (net (code "102") (name "unconnected-(SIM900TECQ-B-Pad24)") (class "Default")
      (node (ref "SIM900TEC") (pin "24") (pinfunction "B_24") (pintype "passive"))
    )
    (net (code "103") (name "unconnected-(SIM900TECS-B-Pad26)") (class "Default")
      (node (ref "SIM900TEC") (pin "26") (pinfunction "B_26") (pintype "passive"))
    )
    (net (code "104") (name "unconnected-(SIM900TECU-B-Pad28)") (class "Default")
      (node (ref "SIM900TEC") (pin "28") (pinfunction "B_28") (pintype "passive"))
    )
    (net (code "105") (name "unconnected-(SIM900TECX-B-Pad30)") (class "Default")
      (node (ref "SIM900TEC") (pin "30") (pinfunction "B_30") (pintype "passive"))
    )
    (net (code "106") (name "unconnected-(SIM900TECZ-B-Pad32)") (class "Default")
      (node (ref "SIM900TEC") (pin "32") (pinfunction "B_32") (pintype "passive"))
    )
    (net (code "107") (name "unconnected-(U$2-RAW-Pad24)") (class "Default")
      (node (ref "U$2") (pin "24") (pinfunction "RAW_24") (pintype "bidirectional"))
    )
    (net (code "108") (name "unconnected-(U$2-RST-Pad3)") (class "Default")
      (node (ref "U$2") (pin "3") (pinfunction "RST_3") (pintype "bidirectional"))
    )
    (net (code "109") (name "unconnected-(U$2-RST-Pad22)") (class "Default")
      (node (ref "U$2") (pin "22") (pinfunction "RST_22") (pintype "bidirectional"))
    )
    (net (code "110") (name "unconnected-(U1-~{SAG}-Pad13)") (class "Default")
      (node (ref "U1") (pin "13") (pinfunction "~{SAG}_13") (pintype "bidirectional"))
    )
  )
)
